# YTN1-E608_Main_V1_4.net
KiCad netlist of a schematic drawn in Altium Designer
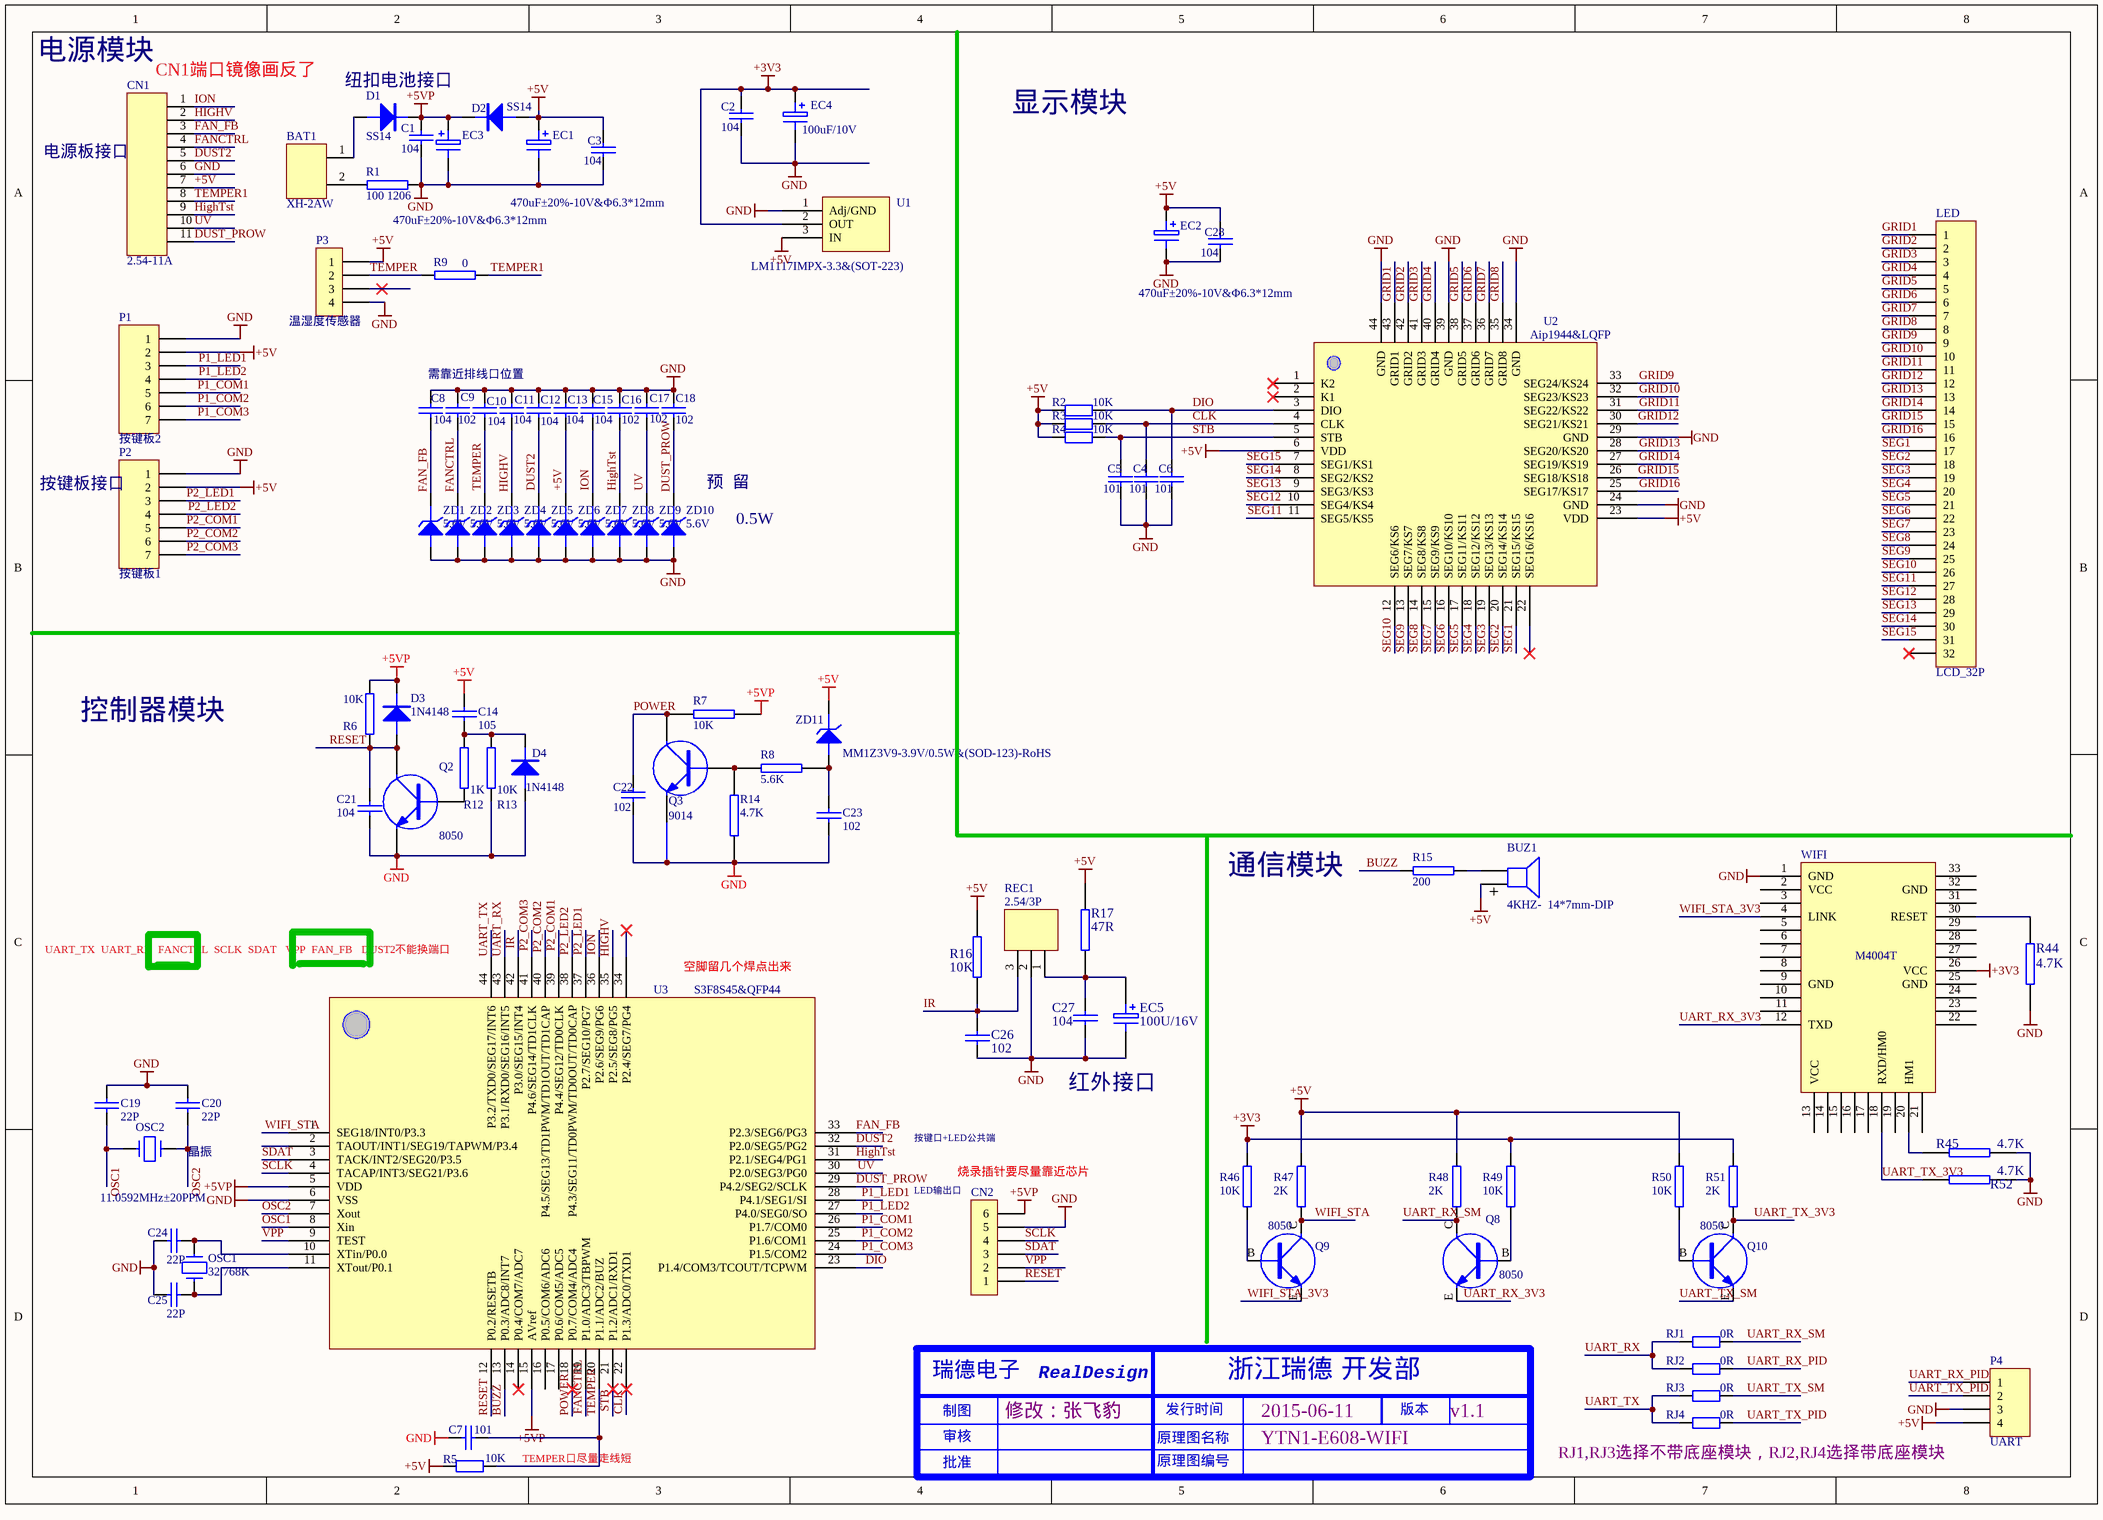
[diagram p0: YTN1-E608(Main)V1.4显示板..schdoc]

(export (version "E")
  (design (tool "Eeschema 10.0.6"))
  (components
    (comp (ref "BAT1") (value "XH-2AW") (footprint "XH-2AW-1") (libsource (lib "*") (part "250-2A")))
    (comp (ref "BUZ1")
      (value "4KHZ-  14*7mm-DIP")
      (footprint "BUZ4K-BCE")
      (libsource (lib "*") (part "SPEAKER"))
    )
    (comp (ref "C1") (value "104") (footprint "0805C") (libsource (lib "*") (part "CAP")))
    (comp (ref "C2") (value "104") (footprint "0805C") (libsource (lib "*") (part "CAP")))
    (comp (ref "C3") (value "104") (footprint "0805C") (libsource (lib "*") (part "CAP")))
    (comp (ref "C4")
      (value "101")
      (footprint "0805C")
      (description "瓷片电容、独石电容")
      (libsource (lib "*") (part "CAP"))
    )
    (comp (ref "C5")
      (value "101")
      (footprint "0805C")
      (description "瓷片电容、独石电容")
      (libsource (lib "*") (part "CAP"))
    )
    (comp (ref "C6")
      (value "101")
      (footprint "0805C")
      (description "瓷片电容、独石电容")
      (libsource (lib "*") (part "CAP"))
    )
    (comp (ref "C7")
      (value "101")
      (footprint "0805C")
      (description "瓷片电容、独石电容")
      (libsource (lib "*") (part "CAP"))
    )
    (comp (ref "C8")
      (value "104")
      (footprint "0805C")
      (description "瓷片电容、独石电容")
      (libsource (lib "*") (part "CAP"))
    )
    (comp (ref "C9")
      (value "102")
      (footprint "0805C")
      (description "瓷片电容、独石电容")
      (libsource (lib "*") (part "CAP"))
    )
    (comp (ref "C10")
      (value "104")
      (footprint "0805C")
      (description "瓷片电容、独石电容")
      (libsource (lib "*") (part "CAP"))
    )
    (comp (ref "C11")
      (value "104")
      (footprint "0805C")
      (description "瓷片电容、独石电容")
      (libsource (lib "*") (part "CAP"))
    )
    (comp (ref "C12")
      (value "104")
      (footprint "0805C")
      (description "瓷片电容、独石电容")
      (libsource (lib "*") (part "CAP"))
    )
    (comp (ref "C13")
      (value "104")
      (footprint "0805C")
      (description "瓷片电容、独石电容")
      (libsource (lib "*") (part "CAP"))
    )
    (comp (ref "C14")
      (value "105")
      (footprint "0805C")
      (description "瓷片电容、独石电容")
      (libsource (lib "*") (part "CAP"))
    )
    (comp (ref "C15")
      (value "104")
      (footprint "0805C")
      (description "瓷片电容、独石电容")
      (libsource (lib "*") (part "CAP"))
    )
    (comp (ref "C16")
      (value "102")
      (footprint "0805C")
      (description "瓷片电容、独石电容")
      (libsource (lib "*") (part "CAP"))
    )
    (comp (ref "C17")
      (value "102")
      (footprint "0805C")
      (description "瓷片电容、独石电容")
      (libsource (lib "*") (part "CAP"))
    )
    (comp (ref "C18")
      (value "102")
      (footprint "0805C")
      (description "瓷片电容、独石电容")
      (libsource (lib "*") (part "CAP"))
    )
    (comp (ref "C19")
      (value "22P")
      (footprint "0805C")
      (description "瓷片电容、独石电容")
      (libsource (lib "*") (part "CAP"))
    )
    (comp (ref "C20")
      (value "22P")
      (footprint "0805C")
      (description "瓷片电容、独石电容")
      (libsource (lib "*") (part "CAP"))
    )
    (comp (ref "C21")
      (value "104")
      (footprint "0805C")
      (description "瓷片电容、独石电容")
      (libsource (lib "*") (part "CAP"))
    )
    (comp (ref "C22")
      (value "102")
      (footprint "0805C")
      (description "瓷片电容、独石电容")
      (libsource (lib "*") (part "CAP"))
    )
    (comp (ref "C23")
      (value "102")
      (footprint "0805C")
      (description "瓷片电容、独石电容")
      (libsource (lib "*") (part "CAP"))
    )
    (comp (ref "C24") (value "22P") (footprint "0805C") (libsource (lib "*") (part "CAP")))
    (comp (ref "C25") (value "22P") (footprint "0805C") (libsource (lib "*") (part "CAP")))
    (comp (ref "C26")
      (value "102")
      (footprint "0805C")
      (description "Capacitor")
      (libsource (lib "") (part "CAP_1"))
    )
    (comp (ref "C27")
      (value "104")
      (footprint "0805C")
      (description "Capacitor")
      (libsource (lib "") (part "CAP_1"))
    )
    (comp (ref "C28") (value "104") (footprint "0805C") (libsource (lib "*") (part "CAP")))
    (comp (ref "CN1") (value "2.54-11A") (footprint "XH-11AW-1") (libsource (lib "*") (part "3.96-11A")))
    (comp (ref "CN2")
      (value "~")
      (footprint "SIP-6P")
      (description "Connector")
      (libsource (lib "*") (part "CON6"))
    )
    (comp (ref "D1")
      (value "SS14")
      (footprint "SMA")
      (description "整流二极管、开关二极管、肖特基二极管、快恢复二极管")
      (libsource (lib "*") (part "DIODE"))
    )
    (comp (ref "D2")
      (value "SS14")
      (footprint "SMA")
      (description "整流二极管、开关二极管、肖特基二极管、快恢复二极管")
      (libsource (lib "*") (part "DIODE"))
    )
    (comp (ref "D3")
      (value "1N4148")
      (footprint "SOD-123")
      (description "整流二极管、开关二极管、肖特基二极管、快恢复二极管")
      (libsource (lib "*") (part "DIODE"))
    )
    (comp (ref "D4")
      (value "1N4148")
      (footprint "SOD-123")
      (description "整流二极管、开关二极管、肖特基二极管、快恢复二极管")
      (libsource (lib "*") (part "DIODE"))
    )
    (comp (ref "EC1")
      (value "470uF±20%-10V&Φ6.3*12mm")
      (footprint "470UF10V-AI")
      (description "电解电容正极为\"1\"号脚")
      (libsource (lib "*") (part "ELECTRO"))
    )
    (comp (ref "EC2")
      (value "470uF±20%-10V&Φ6.3*12mm")
      (footprint "470UF10V-AI")
      (description "电解电容正极为\"1\"号脚")
      (libsource (lib "*") (part "ELECTRO"))
    )
    (comp (ref "EC3")
      (value "470uF±20%-10V&Φ6.3*12mm")
      (footprint "470UF10V-AI")
      (libsource (lib "") (part "ELECTRO1_1"))
    )
    (comp (ref "EC4") (value "100uF/10V") (footprint "100UF10V-AI") (libsource (lib "") (part "ELECTRO1_1")))
    (comp (ref "EC5")
      (value "100U/16V")
      (footprint "100UF16V-AI")
      (description "Electrolytic Capacitor")
      (libsource (lib "*") (part "ELECTRO1"))
    )
    (comp (ref "LED") (value "LCD_32P") (footprint "HYH") (libsource (lib "*") (part "LCD_32P")))
    (comp (ref "OSC1")
      (value "32.768K")
      (footprint "32.768J")
      (description "Crystal")
      (libsource (lib "*") (part "CRYSTAL"))
    )
    (comp (ref "OSC2")
      (value "11.0592MHz±20PPM")
      (footprint "CSA4.19MG")
      (description "Crystal")
      (libsource (lib "") (part "CRYSTAL_1"))
    )
    (comp (ref "P1")
      (value "按键板2")
      (footprint "XH-7AW-1")
      (description "Header, 7-Pin")
      (fields (field (name "PUBLISHER") "Altium Limited"))
      (libsource (lib "*") (part "Header 7"))
    )
    (comp (ref "P2")
      (value "按键板1")
      (footprint "XH-7AW-1")
      (description "Header, 7-Pin")
      (fields (field (name "PUBLISHER") "Altium Limited"))
      (libsource (lib "*") (part "Header 7"))
    )
    (comp (ref "P3")
      (value "温湿度传感器")
      (footprint "XH-4AW-1")
      (description "Connector")
      (libsource (lib "*") (part "CON4"))
    )
    (comp (ref "P4")
      (value "UART")
      (footprint "HDR1X4")
      (description "Header, 4-Pin")
      (fields (field (name "PUBLISHER") "Altium Limited"))
      (libsource (lib "Miscellaneous Connectors") (part "Header 4"))
    )
    (comp (ref "Q2")
      (value "8050")
      (footprint "SOT-23-S")
      (description "晶体管")
      (libsource (lib "") (part "NPN_1"))
    )
    (comp (ref "Q3")
      (value "9014")
      (footprint "SOT-23-S")
      (description "晶体管")
      (libsource (lib "") (part "NPN_1"))
    )
    (comp (ref "Q8")
      (value "8050")
      (footprint "SOT-23-S")
      (description "NPN Transistor")
      (libsource (lib "*") (part "NPN"))
    )
    (comp (ref "Q9")
      (value "8050")
      (footprint "SOT-23-S")
      (description "NPN Transistor")
      (libsource (lib "*") (part "NPN"))
    )
    (comp (ref "Q10")
      (value "8050")
      (footprint "SOT-23-S")
      (description "NPN Transistor")
      (libsource (lib "*") (part "NPN"))
    )
    (comp (ref "R1") (value "100 1206") (footprint "1206R") (libsource (lib "") (part "RES2_1")))
    (comp (ref "R2")
      (value "10K")
      (footprint "0805R")
      (description "Resistor")
      (fields (field (name "Comment") "Res2") (field (name "PUBLISHER") "Altium Limited"))
      (libsource (lib "*") (part "Res2"))
    )
    (comp (ref "R3")
      (value "10K")
      (footprint "0805R")
      (description "Resistor")
      (fields (field (name "Comment") "Res2") (field (name "PUBLISHER") "Altium Limited"))
      (libsource (lib "*") (part "Res2"))
    )
    (comp (ref "R4")
      (value "10K")
      (footprint "0805R")
      (description "Resistor")
      (fields (field (name "Comment") "Res2") (field (name "PUBLISHER") "Altium Limited"))
      (libsource (lib "") (part "Res2_1"))
    )
    (comp (ref "R5")
      (value "10K")
      (footprint "0805R")
      (description "Resistor")
      (fields (field (name "Comment") "Res2") (field (name "PUBLISHER") "Altium Limited"))
      (libsource (lib "*") (part "Res2"))
    )
    (comp (ref "R6") (value "10K") (footprint "0805R") (libsource (lib "") (part "RES2_1")))
    (comp (ref "R7") (value "10K") (footprint "0805R") (libsource (lib "*") (part "R")))
    (comp (ref "R8") (value "5.6K") (footprint "0805R") (libsource (lib "*") (part "R")))
    (comp (ref "R9") (value "0") (footprint "0805R") (libsource (lib "") (part "RES2_1")))
    (comp (ref "R12") (value "1K") (footprint "0805R") (libsource (lib "") (part "RES2_1")))
    (comp (ref "R13") (value "10K") (footprint "0805R") (libsource (lib "") (part "RES2_1")))
    (comp (ref "R14") (value "4.7K") (footprint "0805R") (libsource (lib "*") (part "R")))
    (comp (ref "R15") (value "200") (footprint "0805R") (libsource (lib "") (part "RES2_1")))
    (comp (ref "R16") (value "10K") (footprint "0805R") (libsource (lib "*") (part "RES2")))
    (comp (ref "R17") (value "47R") (footprint "0805-1") (libsource (lib "*") (part "RES2")))
    (comp (ref "R44") (value "4.7K") (footprint "0805R") (libsource (lib "*") (part "RES2")))
    (comp (ref "R45") (value "4.7K") (footprint "0805R") (libsource (lib "*") (part "RES2")))
    (comp (ref "R46") (value "10K") (footprint "0805R") (libsource (lib "") (part "RES2_1")))
    (comp (ref "R47") (value "2K") (footprint "0805R") (libsource (lib "") (part "RES2_1")))
    (comp (ref "R48") (value "2K") (footprint "0805R") (libsource (lib "") (part "RES2_1")))
    (comp (ref "R49") (value "10K") (footprint "0805R") (libsource (lib "") (part "RES2_1")))
    (comp (ref "R50") (value "10K") (footprint "0805R") (libsource (lib "") (part "RES2_1")))
    (comp (ref "R51") (value "2K") (footprint "0805R") (libsource (lib "") (part "RES2_1")))
    (comp (ref "R52") (value "4.7K") (footprint "0805R") (libsource (lib "*") (part "RES2")))
    (comp (ref "REC1") (value "2.54/3P") (footprint "XH-3AW-1") (libsource (lib "*") (part "3.96-3A")))
    (comp (ref "RJ1")
      (value "0R")
      (footprint "AXIAL-0.4")
      (description "Resistor")
      (fields (field (name "PUBLISHER") "Altium Limited"))
      (libsource (lib "Miscellaneous Devices") (part "Res2"))
    )
    (comp (ref "RJ2")
      (value "0R")
      (footprint "AXIAL-0.4")
      (description "Resistor")
      (fields (field (name "PUBLISHER") "Altium Limited"))
      (libsource (lib "Miscellaneous Devices") (part "Res2"))
    )
    (comp (ref "RJ3")
      (value "0R")
      (footprint "AXIAL-0.4")
      (description "Resistor")
      (fields (field (name "PUBLISHER") "Altium Limited"))
      (libsource (lib "Miscellaneous Devices") (part "Res2"))
    )
    (comp (ref "RJ4")
      (value "0R")
      (footprint "AXIAL-0.4")
      (description "Resistor")
      (fields (field (name "PUBLISHER") "Altium Limited"))
      (libsource (lib "Miscellaneous Devices") (part "Res2"))
    )
    (comp (ref "U1") (value "LM1117IMPX-3.3&(SOT-223)") (libsource (lib "*") (part "LM1117-3.3V")))
    (comp (ref "U2") (value "Aip1944&LQFP") (footprint "QFP44") (libsource (lib "*") (part "Aip1944&LQFP")))
    (comp (ref "U3") (value "S3F8S45&QFP44") (footprint "QFP44") (libsource (lib "*") (part "S3F8S45&QFP44")))
    (comp (ref "WIFI") (value "M4004T") (footprint "WIFI") (libsource (lib "*") (part "WIFI")))
    (comp (ref "ZD1") (value "5.6V") (footprint "SOD-123") (libsource (lib "*") (part "ZD")))
    (comp (ref "ZD2") (value "5.6V") (footprint "SOD-123") (libsource (lib "*") (part "ZD")))
    (comp (ref "ZD3") (value "5.6V") (footprint "SOD-123") (libsource (lib "*") (part "ZD")))
    (comp (ref "ZD4") (value "5.6V") (footprint "SOD-123") (libsource (lib "*") (part "ZD")))
    (comp (ref "ZD5") (value "5.6V") (footprint "SOD-123") (libsource (lib "*") (part "ZD")))
    (comp (ref "ZD6") (value "5.6V") (footprint "SOD-123") (libsource (lib "*") (part "ZD")))
    (comp (ref "ZD7") (value "5.6V") (footprint "SOD-123") (libsource (lib "*") (part "ZD")))
    (comp (ref "ZD8") (value "5.6V") (footprint "SOD-123") (libsource (lib "*") (part "ZD")))
    (comp (ref "ZD9") (value "5.6V") (footprint "SOD-123") (libsource (lib "*") (part "ZD")))
    (comp (ref "ZD10") (value "5.6V") (footprint "SOD-123") (libsource (lib "*") (part "ZD")))
    (comp (ref "ZD11")
      (value "MM1Z3V9-3.9V/0.5W&(SOD-123)-RoHS")
      (footprint "SOD-123")
      (libsource (lib "*") (part "ZD"))
    )
  )
  (nets
    (net (code "1") (name "+3V3") (class "Default")
      (node (ref "C2") (pin "1") (pintype "passive"))
      (node (ref "EC4") (pin "1") (pintype "passive"))
      (node (ref "R46") (pin "1") (pintype "passive"))
      (node (ref "R49") (pin "1") (pintype "passive"))
      (node (ref "R51") (pin "1") (pintype "passive"))
      (node (ref "U1") (pin "2") (pinfunction "OUT_2") (pintype "passive"))
      (node (ref "WIFI") (pin "26") (pinfunction "VCC_26") (pintype "passive"))
    )
    (net (code "2") (name "+5V") (class "Default")
      (node (ref "BUZ1") (pin "1") (pinfunction "1_1") (pintype "passive"))
      (node (ref "C13") (pin "2") (pintype "passive"))
      (node (ref "C14") (pin "1") (pintype "passive"))
      (node (ref "C28") (pin "1") (pintype "passive"))
      (node (ref "C3") (pin "1") (pintype "passive"))
      (node (ref "CN1") (pin "7") (pinfunction "7_7") (pintype "passive"))
      (node (ref "D2") (pin "A") (pintype "passive"))
      (node (ref "EC1") (pin "1") (pintype "passive"))
      (node (ref "EC2") (pin "1") (pintype "passive"))
      (node (ref "P1") (pin "2") (pinfunction "2_2") (pintype "passive"))
      (node (ref "P2") (pin "2") (pinfunction "2_2") (pintype "passive"))
      (node (ref "P3") (pin "1") (pinfunction "1_1") (pintype "passive"))
      (node (ref "P4") (pin "4") (pinfunction "4_4") (pintype "passive"))
      (node (ref "R16") (pin "2") (pinfunction "2_2") (pintype "passive"))
      (node (ref "R17") (pin "2") (pinfunction "2_2") (pintype "passive"))
      (node (ref "R2") (pin "2") (pinfunction "2_2") (pintype "passive"))
      (node (ref "R3") (pin "2") (pinfunction "2_2") (pintype "passive"))
      (node (ref "R4") (pin "1") (pinfunction "1_1") (pintype "passive"))
      (node (ref "R47") (pin "1") (pintype "passive"))
      (node (ref "R48") (pin "1") (pintype "passive"))
      (node (ref "R5") (pin "2") (pinfunction "2_2") (pintype "passive"))
      (node (ref "R50") (pin "1") (pintype "passive"))
      (node (ref "U1") (pin "3") (pinfunction "IN_3") (pintype "passive"))
      (node (ref "U2") (pin "23") (pinfunction "VDD_23") (pintype "passive"))
      (node (ref "U2") (pin "6") (pinfunction "VDD_6") (pintype "passive"))
      (node (ref "ZD11") (pin "K") (pintype "passive"))
      (node (ref "ZD6") (pin "K") (pintype "passive"))
    )
    (net (code "3") (name "+5VP") (class "Default")
      (node (ref "C1") (pin "1") (pintype "passive"))
      (node (ref "CN2") (pin "6") (pinfunction "6_6") (pintype "passive"))
      (node (ref "D1") (pin "K") (pintype "passive"))
      (node (ref "D2") (pin "K") (pintype "passive"))
      (node (ref "D3") (pin "K") (pintype "passive"))
      (node (ref "EC3") (pin "1") (pintype "passive"))
      (node (ref "R6") (pin "2") (pintype "passive"))
      (node (ref "R7") (pin "1") (pinfunction "1_1") (pintype "passive"))
      (node (ref "U3") (pin "15") (pinfunction "AVref_15") (pintype "passive"))
      (node (ref "U3") (pin "5") (pinfunction "VDD_5") (pintype "passive"))
    )
    (net (code "4") (name "/BUZZ") (class "Default")
      (node (ref "R15") (pin "1") (pintype "passive"))
      (node (ref "U3") (pin "13") (pinfunction "P0.3/ADC8/INT7_13") (pintype "passive"))
    )
    (net (code "5") (name "/CLK") (class "Default")
      (node (ref "C4") (pin "1") (pintype "passive"))
      (node (ref "R3") (pin "1") (pinfunction "1_1") (pintype "passive"))
      (node (ref "U2") (pin "4") (pinfunction "CLK_4") (pintype "passive"))
      (node (ref "U3") (pin "22") (pinfunction "P1.3/ADC0/TXD1_22") (pintype "passive"))
    )
    (net (code "6") (name "/DIO") (class "Default")
      (node (ref "C6") (pin "1") (pintype "passive"))
      (node (ref "R2") (pin "1") (pinfunction "1_1") (pintype "passive"))
      (node (ref "U2") (pin "3") (pinfunction "DIO_3") (pintype "passive"))
      (node (ref "U3") (pin "23") (pinfunction "P1.4/COM3/TCOUT/TCPWM_23") (pintype "passive"))
    )
    (net (code "7") (name "/DUST2") (class "Default")
      (node (ref "C12") (pin "2") (pintype "passive"))
      (node (ref "CN1") (pin "5") (pinfunction "5_5") (pintype "passive"))
      (node (ref "U3") (pin "32") (pinfunction "P2.0/SEG5/PG2_32") (pintype "passive"))
      (node (ref "ZD5") (pin "K") (pintype "passive"))
    )
    (net (code "8") (name "/DUST_PROW") (class "Default")
      (node (ref "C18") (pin "2") (pintype "passive"))
      (node (ref "CN1") (pin "11") (pinfunction "11_11") (pintype "passive"))
      (node (ref "U3") (pin "29") (pinfunction "P4.2/SEG2/SCLK_29") (pintype "passive"))
      (node (ref "ZD10") (pin "K") (pintype "passive"))
    )
    (net (code "9") (name "/FANCTRL") (class "Default")
      (node (ref "C9") (pin "2") (pintype "passive"))
      (node (ref "CN1") (pin "4") (pinfunction "4_4") (pintype "passive"))
      (node (ref "U3") (pin "19") (pinfunction "P1.0/ADC3/TBPWM_19") (pintype "passive"))
      (node (ref "ZD2") (pin "K") (pintype "passive"))
    )
    (net (code "10") (name "/FAN_FB") (class "Default")
      (node (ref "C8") (pin "2") (pintype "passive"))
      (node (ref "CN1") (pin "3") (pinfunction "3_3") (pintype "passive"))
      (node (ref "U3") (pin "33") (pinfunction "P2.3/SEG6/PG3_33") (pintype "passive"))
      (node (ref "ZD1") (pin "K") (pintype "passive"))
    )
    (net (code "11") (name "/GRID1") (class "Default")
      (node (ref "LED") (pin "1") (pinfunction "1_1") (pintype "passive"))
      (node (ref "U2") (pin "43") (pinfunction "GRID1_43") (pintype "passive"))
    )
    (net (code "12") (name "/GRID2") (class "Default")
      (node (ref "LED") (pin "2") (pinfunction "2_2") (pintype "passive"))
      (node (ref "U2") (pin "42") (pinfunction "GRID2_42") (pintype "passive"))
    )
    (net (code "13") (name "/GRID3") (class "Default")
      (node (ref "LED") (pin "3") (pinfunction "3_3") (pintype "passive"))
      (node (ref "U2") (pin "41") (pinfunction "GRID3_41") (pintype "passive"))
    )
    (net (code "14") (name "/GRID4") (class "Default")
      (node (ref "LED") (pin "4") (pinfunction "4_4") (pintype "passive"))
      (node (ref "U2") (pin "40") (pinfunction "GRID4_40") (pintype "passive"))
    )
    (net (code "15") (name "/GRID5") (class "Default")
      (node (ref "LED") (pin "5") (pinfunction "5_5") (pintype "passive"))
      (node (ref "U2") (pin "38") (pinfunction "GRID5_38") (pintype "passive"))
    )
    (net (code "16") (name "/GRID6") (class "Default")
      (node (ref "LED") (pin "6") (pinfunction "6_6") (pintype "passive"))
      (node (ref "U2") (pin "37") (pinfunction "GRID6_37") (pintype "passive"))
    )
    (net (code "17") (name "/GRID7") (class "Default")
      (node (ref "LED") (pin "7") (pinfunction "7_7") (pintype "passive"))
      (node (ref "U2") (pin "36") (pinfunction "GRID7_36") (pintype "passive"))
    )
    (net (code "18") (name "/GRID8") (class "Default")
      (node (ref "LED") (pin "8") (pinfunction "8_8") (pintype "passive"))
      (node (ref "U2") (pin "35") (pinfunction "GRID8_35") (pintype "passive"))
    )
    (net (code "19") (name "/GRID9") (class "Default")
      (node (ref "LED") (pin "9") (pinfunction "9_9") (pintype "passive"))
      (node (ref "U2") (pin "33") (pinfunction "SEG24/KS24_33") (pintype "passive"))
    )
    (net (code "20") (name "/GRID10") (class "Default")
      (node (ref "LED") (pin "10") (pinfunction "10_10") (pintype "passive"))
      (node (ref "U2") (pin "32") (pinfunction "SEG23/KS23_32") (pintype "passive"))
    )
    (net (code "21") (name "/GRID11") (class "Default")
      (node (ref "LED") (pin "11") (pinfunction "11_11") (pintype "passive"))
      (node (ref "U2") (pin "31") (pinfunction "SEG22/KS22_31") (pintype "passive"))
    )
    (net (code "22") (name "/GRID12") (class "Default")
      (node (ref "LED") (pin "12") (pinfunction "12_12") (pintype "passive"))
      (node (ref "U2") (pin "30") (pinfunction "SEG21/KS21_30") (pintype "passive"))
    )
    (net (code "23") (name "/GRID13") (class "Default")
      (node (ref "LED") (pin "13") (pinfunction "13_13") (pintype "passive"))
      (node (ref "U2") (pin "28") (pinfunction "SEG20/KS20_28") (pintype "passive"))
    )
    (net (code "24") (name "/GRID14") (class "Default")
      (node (ref "LED") (pin "14") (pinfunction "14_14") (pintype "passive"))
      (node (ref "U2") (pin "27") (pinfunction "SEG19/KS19_27") (pintype "passive"))
    )
    (net (code "25") (name "/GRID15") (class "Default")
      (node (ref "LED") (pin "15") (pinfunction "15_15") (pintype "passive"))
      (node (ref "U2") (pin "26") (pinfunction "SEG18/KS18_26") (pintype "passive"))
    )
    (net (code "26") (name "/GRID16") (class "Default")
      (node (ref "LED") (pin "16") (pinfunction "16_16") (pintype "passive"))
      (node (ref "U2") (pin "25") (pinfunction "SEG17/KS17_25") (pintype "passive"))
    )
    (net (code "27") (name "/HIGHV") (class "Default")
      (node (ref "C11") (pin "2") (pintype "passive"))
      (node (ref "CN1") (pin "2") (pinfunction "2_2") (pintype "passive"))
      (node (ref "U3") (pin "35") (pinfunction "P2.5/SEG8/PG5_35") (pintype "passive"))
      (node (ref "ZD4") (pin "K") (pintype "passive"))
    )
    (net (code "28") (name "/HighTst") (class "Default")
      (node (ref "C16") (pin "2") (pintype "passive"))
      (node (ref "CN1") (pin "9") (pinfunction "9_9") (pintype "passive"))
      (node (ref "U3") (pin "31") (pinfunction "P2.1/SEG4/PG1_31") (pintype "passive"))
      (node (ref "ZD8") (pin "K") (pintype "passive"))
    )
    (net (code "29") (name "/ION") (class "Default")
      (node (ref "C15") (pin "2") (pintype "passive"))
      (node (ref "CN1") (pin "1") (pinfunction "1_1") (pintype "passive"))
      (node (ref "U3") (pin "36") (pinfunction "P2.6/SEG9/PG6_36") (pintype "passive"))
      (node (ref "ZD7") (pin "K") (pintype "passive"))
    )
    (net (code "30") (name "/IR") (class "Default")
      (node (ref "C26") (pin "1") (pinfunction "1_1") (pintype "passive"))
      (node (ref "R16") (pin "1") (pinfunction "1_1") (pintype "passive"))
      (node (ref "REC1") (pin "3") (pinfunction "20_3") (pintype "passive"))
      (node (ref "U3") (pin "42") (pinfunction "P3.0/SEG15/INT4_42") (pintype "passive"))
    )
    (net (code "31") (name "/OSC1") (class "Default")
      (node (ref "C19") (pin "1") (pintype "passive"))
      (node (ref "OSC2") (pin "1") (pinfunction "1_1") (pintype "passive"))
      (node (ref "U3") (pin "8") (pinfunction "Xin_8") (pintype "passive"))
    )
    (net (code "32") (name "/OSC2") (class "Default")
      (node (ref "C20") (pin "1") (pintype "passive"))
      (node (ref "OSC2") (pin "3") (pinfunction "3_3") (pintype "passive"))
      (node (ref "U3") (pin "7") (pinfunction "Xout_7") (pintype "passive"))
    )
    (net (code "33") (name "/P1_COM1") (class "Default")
      (node (ref "P1") (pin "5") (pinfunction "5_5") (pintype "passive"))
      (node (ref "U3") (pin "26") (pinfunction "P1.7/COM0_26") (pintype "passive"))
    )
    (net (code "34") (name "/P1_COM2") (class "Default")
      (node (ref "P1") (pin "6") (pinfunction "6_6") (pintype "passive"))
      (node (ref "U3") (pin "25") (pinfunction "P1.6/COM1_25") (pintype "passive"))
    )
    (net (code "35") (name "/P1_COM3") (class "Default")
      (node (ref "P1") (pin "7") (pinfunction "7_7") (pintype "passive"))
      (node (ref "U3") (pin "24") (pinfunction "P1.5/COM2_24") (pintype "passive"))
    )
    (net (code "36") (name "/P1_LED1") (class "Default")
      (node (ref "P1") (pin "3") (pinfunction "3_3") (pintype "passive"))
      (node (ref "U3") (pin "28") (pinfunction "P4.1/SEG1/SI_28") (pintype "passive"))
    )
    (net (code "37") (name "/P1_LED2") (class "Default")
      (node (ref "P1") (pin "4") (pinfunction "4_4") (pintype "passive"))
      (node (ref "U3") (pin "27") (pinfunction "P4.0/SEG0/SO_27") (pintype "passive"))
    )
    (net (code "38") (name "/P2_COM1") (class "Default")
      (node (ref "P2") (pin "5") (pinfunction "5_5") (pintype "passive"))
      (node (ref "U3") (pin "39") (pinfunction "P4.4/SEG12/TD0CLK_39") (pintype "passive"))
    )
    (net (code "39") (name "/P2_COM2") (class "Default")
      (node (ref "P2") (pin "6") (pinfunction "6_6") (pintype "passive"))
      (node (ref "U3") (pin "40") (pinfunction "P4.5/SEG13/TD1PWM/TD1OUT/TD1CAP_40") (pintype "passive"))
    )
    (net (code "40") (name "/P2_COM3") (class "Default")
      (node (ref "P2") (pin "7") (pinfunction "7_7") (pintype "passive"))
      (node (ref "U3") (pin "41") (pinfunction "P4.6/SEG14/TD1CLK_41") (pintype "passive"))
    )
    (net (code "41") (name "/P2_LED1") (class "Default")
      (node (ref "P2") (pin "3") (pinfunction "3_3") (pintype "passive"))
      (node (ref "U3") (pin "37") (pinfunction "P2.7/SEG10/PG7_37") (pintype "passive"))
    )
    (net (code "42") (name "/P2_LED2") (class "Default")
      (node (ref "P2") (pin "4") (pinfunction "4_4") (pintype "passive"))
      (node (ref "U3") (pin "38") (pinfunction "P4.3/SEG11/TD0PWM/TD0OUT/TD0CAP_38") (pintype "passive"))
    )
    (net (code "43") (name "/POWER") (class "Default")
      (node (ref "C22") (pin "1") (pintype "passive"))
      (node (ref "Q3") (pin "C") (pintype "passive"))
      (node (ref "R7") (pin "2") (pinfunction "2_2") (pintype "passive"))
      (node (ref "U3") (pin "18") (pinfunction "P0.7/COM4/ADC4_18") (pintype "passive"))
    )
    (net (code "44") (name "/RESET") (class "Default")
      (node (ref "C21") (pin "1") (pintype "passive"))
      (node (ref "CN2") (pin "1") (pinfunction "1_1") (pintype "passive"))
      (node (ref "D3") (pin "A") (pintype "passive"))
      (node (ref "Q2") (pin "C") (pintype "passive"))
      (node (ref "R6") (pin "1") (pintype "passive"))
      (node (ref "U3") (pin "12") (pinfunction "P0.2/RESETB_12") (pintype "passive"))
    )
    (net (code "45") (name "/SCLK") (class "Default")
      (node (ref "CN2") (pin "4") (pinfunction "4_4") (pintype "passive"))
      (node (ref "U3") (pin "4") (pinfunction "TACAP/INT3/SEG21/P3.6_4") (pintype "passive"))
    )
    (net (code "46") (name "/SDAT") (class "Default")
      (node (ref "CN2") (pin "3") (pinfunction "3_3") (pintype "passive"))
      (node (ref "U3") (pin "3") (pinfunction "TACK/INT2/SEG20/P3.5_3") (pintype "passive"))
    )
    (net (code "47") (name "/SEG1") (class "Default")
      (node (ref "LED") (pin "17") (pinfunction "17_17") (pintype "passive"))
      (node (ref "U2") (pin "21") (pinfunction "SEG15/KS15_21") (pintype "passive"))
    )
    (net (code "48") (name "/SEG2") (class "Default")
      (node (ref "LED") (pin "18") (pinfunction "18_18") (pintype "passive"))
      (node (ref "U2") (pin "20") (pinfunction "SEG14/KS14_20") (pintype "passive"))
    )
    (net (code "49") (name "/SEG3") (class "Default")
      (node (ref "LED") (pin "19") (pinfunction "19_19") (pintype "passive"))
      (node (ref "U2") (pin "19") (pinfunction "SEG13/KS13_19") (pintype "passive"))
    )
    (net (code "50") (name "/SEG4") (class "Default")
      (node (ref "LED") (pin "20") (pinfunction "20_20") (pintype "passive"))
      (node (ref "U2") (pin "18") (pinfunction "SEG12/KS12_18") (pintype "passive"))
    )
    (net (code "51") (name "/SEG5") (class "Default")
      (node (ref "LED") (pin "21") (pinfunction "21_21") (pintype "passive"))
      (node (ref "U2") (pin "17") (pinfunction "SEG11/KS11_17") (pintype "passive"))
    )
    (net (code "52") (name "/SEG6") (class "Default")
      (node (ref "LED") (pin "22") (pinfunction "22_22") (pintype "passive"))
      (node (ref "U2") (pin "16") (pinfunction "SEG10/KS10_16") (pintype "passive"))
    )
    (net (code "53") (name "/SEG7") (class "Default")
      (node (ref "LED") (pin "23") (pinfunction "23_23") (pintype "passive"))
      (node (ref "U2") (pin "15") (pinfunction "SEG9/KS9_15") (pintype "passive"))
    )
    (net (code "54") (name "/SEG8") (class "Default")
      (node (ref "LED") (pin "24") (pinfunction "24_24") (pintype "passive"))
      (node (ref "U2") (pin "14") (pinfunction "SEG8/KS8_14") (pintype "passive"))
    )
    (net (code "55") (name "/SEG9") (class "Default")
      (node (ref "LED") (pin "25") (pinfunction "25_25") (pintype "passive"))
      (node (ref "U2") (pin "13") (pinfunction "SEG7/KS7_13") (pintype "passive"))
    )
    (net (code "56") (name "/SEG10") (class "Default")
      (node (ref "LED") (pin "26") (pinfunction "26_26") (pintype "passive"))
      (node (ref "U2") (pin "12") (pinfunction "SEG6/KS6_12") (pintype "passive"))
    )
    (net (code "57") (name "/SEG11") (class "Default")
      (node (ref "LED") (pin "27") (pinfunction "27_27") (pintype "passive"))
      (node (ref "U2") (pin "11") (pinfunction "SEG5/KS5_11") (pintype "passive"))
    )
    (net (code "58") (name "/SEG12") (class "Default")
      (node (ref "LED") (pin "28") (pinfunction "28_28") (pintype "passive"))
      (node (ref "U2") (pin "10") (pinfunction "SEG4/KS4_10") (pintype "passive"))
    )
    (net (code "59") (name "/SEG13") (class "Default")
      (node (ref "LED") (pin "29") (pinfunction "29_29") (pintype "passive"))
      (node (ref "U2") (pin "9") (pinfunction "SEG3/KS3_9") (pintype "passive"))
    )
    (net (code "60") (name "/SEG14") (class "Default")
      (node (ref "LED") (pin "30") (pinfunction "30_30") (pintype "passive"))
      (node (ref "U2") (pin "8") (pinfunction "SEG2/KS2_8") (pintype "passive"))
    )
    (net (code "61") (name "/SEG15") (class "Default")
      (node (ref "LED") (pin "31") (pinfunction "31_31") (pintype "passive"))
      (node (ref "U2") (pin "7") (pinfunction "SEG1/KS1_7") (pintype "passive"))
    )
    (net (code "62") (name "/STB") (class "Default")
      (node (ref "C5") (pin "1") (pintype "passive"))
      (node (ref "R4") (pin "2") (pinfunction "2_2") (pintype "passive"))
      (node (ref "U2") (pin "5") (pinfunction "STB_5") (pintype "passive"))
      (node (ref "U3") (pin "21") (pinfunction "P1.2/ADC1/RXD1_21") (pintype "passive"))
    )
    (net (code "63") (name "/TEMPER") (class "Default")
      (node (ref "C10") (pin "2") (pintype "passive"))
      (node (ref "C7") (pin "1") (pintype "passive"))
      (node (ref "P3") (pin "2") (pinfunction "2_2") (pintype "passive"))
      (node (ref "R5") (pin "1") (pinfunction "1_1") (pintype "passive"))
      (node (ref "R9") (pin "1") (pintype "passive"))
      (node (ref "U3") (pin "20") (pinfunction "P1.1/ADC2/BUZ_20") (pintype "passive"))
      (node (ref "ZD3") (pin "K") (pintype "passive"))
    )
    (net (code "64") (name "/TEMPER1") (class "Default")
      (node (ref "CN1") (pin "8") (pinfunction "8_8") (pintype "passive"))
      (node (ref "R9") (pin "2") (pintype "passive"))
    )
    (net (code "65") (name "/UART_RX") (class "Default")
      (node (ref "RJ1") (pin "1") (pinfunction "1_1") (pintype "passive"))
      (node (ref "RJ2") (pin "1") (pinfunction "1_1") (pintype "passive"))
      (node (ref "U3") (pin "43") (pinfunction "P3.1/RXD0/SEG16/INT5_43") (pintype "passive"))
    )
    (net (code "66") (name "/UART_RX_3V3") (class "Default")
      (node (ref "Q8") (pin "E") (pintype "passive"))
      (node (ref "WIFI") (pin "12") (pinfunction "TXD_12") (pintype "passive"))
    )
    (net (code "67") (name "/UART_RX_PID") (class "Default")
      (node (ref "P4") (pin "1") (pinfunction "1_1") (pintype "passive"))
      (node (ref "RJ2") (pin "2") (pinfunction "2_2") (pintype "passive"))
    )
    (net (code "68") (name "/UART_RX_SM") (class "Default")
      (node (ref "Q8") (pin "C") (pintype "passive"))
      (node (ref "R48") (pin "2") (pintype "passive"))
      (node (ref "RJ1") (pin "2") (pinfunction "2_2") (pintype "passive"))
    )
    (net (code "69") (name "/UART_TX") (class "Default")
      (node (ref "RJ3") (pin "1") (pinfunction "1_1") (pintype "passive"))
      (node (ref "RJ4") (pin "1") (pinfunction "1_1") (pintype "passive"))
      (node (ref "U3") (pin "44") (pinfunction "P3.2/TXD0/SEG17/INT6_44") (pintype "passive"))
    )
    (net (code "70") (name "/UART_TX_3V3") (class "Default")
      (node (ref "Q10") (pin "C") (pintype "passive"))
      (node (ref "R51") (pin "2") (pintype "passive"))
      (node (ref "R52") (pin "2") (pinfunction "2_2") (pintype "passive"))
      (node (ref "WIFI") (pin "18") (pinfunction "RXD/HM0_18") (pintype "passive"))
    )
    (net (code "71") (name "/UART_TX_PID") (class "Default")
      (node (ref "P4") (pin "2") (pinfunction "2_2") (pintype "passive"))
      (node (ref "RJ4") (pin "2") (pinfunction "2_2") (pintype "passive"))
    )
    (net (code "72") (name "/UART_TX_SM") (class "Default")
      (node (ref "Q10") (pin "E") (pintype "passive"))
      (node (ref "RJ3") (pin "2") (pinfunction "2_2") (pintype "passive"))
    )
    (net (code "73") (name "/UV") (class "Default")
      (node (ref "C17") (pin "2") (pintype "passive"))
      (node (ref "CN1") (pin "10") (pinfunction "10_10") (pintype "passive"))
      (node (ref "U3") (pin "30") (pinfunction "P2.0/SEG3/PG0_30") (pintype "passive"))
      (node (ref "ZD9") (pin "K") (pintype "passive"))
    )
    (net (code "74") (name "/VPP") (class "Default")
      (node (ref "CN2") (pin "2") (pinfunction "2_2") (pintype "passive"))
      (node (ref "U3") (pin "9") (pinfunction "TEST_9") (pintype "passive"))
    )
    (net (code "75") (name "/WIFI_STA") (class "Default")
      (node (ref "Q9") (pin "C") (pintype "passive"))
      (node (ref "R47") (pin "2") (pintype "passive"))
      (node (ref "U3") (pin "1") (pinfunction "SEG18/INT0/P3.3_1") (pintype "passive"))
    )
    (net (code "76") (name "/WIFI_STA_3V3") (class "Default")
      (node (ref "Q9") (pin "E") (pintype "passive"))
      (node (ref "WIFI") (pin "4") (pinfunction "LINK_4") (pintype "passive"))
    )
    (net (code "77") (name "GND") (class "Default")
      (node (ref "C1") (pin "2") (pintype "passive"))
      (node (ref "C10") (pin "1") (pintype "passive"))
      (node (ref "C11") (pin "1") (pintype "passive"))
      (node (ref "C12") (pin "1") (pintype "passive"))
      (node (ref "C13") (pin "1") (pintype "passive"))
      (node (ref "C15") (pin "1") (pintype "passive"))
      (node (ref "C16") (pin "1") (pintype "passive"))
      (node (ref "C17") (pin "1") (pintype "passive"))
      (node (ref "C18") (pin "1") (pintype "passive"))
      (node (ref "C19") (pin "2") (pintype "passive"))
      (node (ref "C2") (pin "2") (pintype "passive"))
      (node (ref "C20") (pin "2") (pintype "passive"))
      (node (ref "C21") (pin "2") (pintype "passive"))
      (node (ref "C22") (pin "2") (pintype "passive"))
      (node (ref "C23") (pin "2") (pintype "passive"))
      (node (ref "C24") (pin "1") (pintype "passive"))
      (node (ref "C25") (pin "1") (pintype "passive"))
      (node (ref "C26") (pin "2") (pinfunction "2_2") (pintype "passive"))
      (node (ref "C27") (pin "2") (pinfunction "2_2") (pintype "passive"))
      (node (ref "C28") (pin "2") (pintype "passive"))
      (node (ref "C3") (pin "2") (pintype "passive"))
      (node (ref "C4") (pin "2") (pintype "passive"))
      (node (ref "C5") (pin "2") (pintype "passive"))
      (node (ref "C6") (pin "2") (pintype "passive"))
      (node (ref "C7") (pin "2") (pintype "passive"))
      (node (ref "C8") (pin "1") (pintype "passive"))
      (node (ref "C9") (pin "1") (pintype "passive"))
      (node (ref "CN1") (pin "6") (pinfunction "6_6") (pintype "passive"))
      (node (ref "CN2") (pin "5") (pinfunction "5_5") (pintype "passive"))
      (node (ref "D4") (pin "A") (pintype "passive"))
      (node (ref "EC1") (pin "2") (pintype "passive"))
      (node (ref "EC2") (pin "2") (pintype "passive"))
      (node (ref "EC3") (pin "2") (pintype "passive"))
      (node (ref "EC4") (pin "2") (pintype "passive"))
      (node (ref "EC5") (pin "2") (pinfunction "2_2") (pintype "passive"))
      (node (ref "P1") (pin "1") (pinfunction "1_1") (pintype "passive"))
      (node (ref "P2") (pin "1") (pinfunction "1_1") (pintype "passive"))
      (node (ref "P3") (pin "4") (pinfunction "4_4") (pintype "passive"))
      (node (ref "P4") (pin "3") (pinfunction "3_3") (pintype "passive"))
      (node (ref "Q2") (pin "E") (pintype "passive"))
      (node (ref "Q3") (pin "E") (pintype "passive"))
      (node (ref "R1") (pin "2") (pintype "passive"))
      (node (ref "R13") (pin "1") (pintype "passive"))
      (node (ref "R14") (pin "1") (pinfunction "1_1") (pintype "passive"))
      (node (ref "R44") (pin "2") (pinfunction "2_2") (pintype "passive"))
      (node (ref "R45") (pin "1") (pinfunction "1_1") (pintype "passive"))
      (node (ref "R52") (pin "1") (pinfunction "1_1") (pintype "passive"))
      (node (ref "REC1") (pin "2") (pinfunction "2_2") (pintype "passive"))
      (node (ref "U1") (pin "1") (pinfunction "Adj/GND_1") (pintype "passive"))
      (node (ref "U2") (pin "24") (pinfunction "GND_24") (pintype "passive"))
      (node (ref "U2") (pin "29") (pinfunction "GND_29") (pintype "passive"))
      (node (ref "U2") (pin "34") (pinfunction "GND_34") (pintype "passive"))
      (node (ref "U2") (pin "39") (pinfunction "GND_39") (pintype "passive"))
      (node (ref "U2") (pin "44") (pinfunction "GND_44") (pintype "passive"))
      (node (ref "U3") (pin "6") (pinfunction "VSS_6") (pintype "passive"))
      (node (ref "WIFI") (pin "1") (pinfunction "GND_1") (pintype "passive"))
      (node (ref "ZD1") (pin "A") (pintype "passive"))
      (node (ref "ZD10") (pin "A") (pintype "passive"))
      (node (ref "ZD2") (pin "A") (pintype "passive"))
      (node (ref "ZD3") (pin "A") (pintype "passive"))
      (node (ref "ZD4") (pin "A") (pintype "passive"))
      (node (ref "ZD5") (pin "A") (pintype "passive"))
      (node (ref "ZD6") (pin "A") (pintype "passive"))
      (node (ref "ZD7") (pin "A") (pintype "passive"))
      (node (ref "ZD8") (pin "A") (pintype "passive"))
      (node (ref "ZD9") (pin "A") (pintype "passive"))
    )
    (net (code "78") (name "Net-(BAT1-Pad1)") (class "Default")
      (node (ref "BAT1") (pin "1") (pinfunction "1_1") (pintype "passive"))
      (node (ref "D1") (pin "A") (pintype "passive"))
    )
    (net (code "79") (name "Net-(BAT1-Pad2)") (class "Default")
      (node (ref "BAT1") (pin "2") (pinfunction "2_2") (pintype "passive"))
      (node (ref "R1") (pin "1") (pintype "passive"))
    )
    (net (code "80") (name "Net-(BUZ1-Pad2)") (class "Default")
      (node (ref "BUZ1") (pin "2") (pinfunction "2_2") (pintype "passive"))
      (node (ref "R15") (pin "2") (pintype "passive"))
    )
    (net (code "81") (name "Net-(C14-Pad2)") (class "Default")
      (node (ref "C14") (pin "2") (pintype "passive"))
      (node (ref "D4") (pin "K") (pintype "passive"))
      (node (ref "R12") (pin "2") (pintype "passive"))
      (node (ref "R13") (pin "2") (pintype "passive"))
    )
    (net (code "82") (name "Net-(C23-Pad1)") (class "Default")
      (node (ref "C23") (pin "1") (pintype "passive"))
      (node (ref "R8") (pin "1") (pinfunction "1_1") (pintype "passive"))
      (node (ref "ZD11") (pin "A") (pintype "passive"))
    )
    (net (code "83") (name "Net-(C27-Pad1)") (class "Default")
      (node (ref "C27") (pin "1") (pinfunction "1_1") (pintype "passive"))
      (node (ref "EC5") (pin "1") (pinfunction "1_1") (pintype "passive"))
      (node (ref "R17") (pin "1") (pinfunction "1_1") (pintype "passive"))
      (node (ref "REC1") (pin "1") (pinfunction "1_1") (pintype "passive"))
    )
    (net (code "84") (name "Net-(Q2-PadB)") (class "Default")
      (node (ref "Q2") (pin "B") (pintype "passive"))
      (node (ref "R12") (pin "1") (pintype "passive"))
    )
    (net (code "85") (name "Net-(Q3-PadB)") (class "Default")
      (node (ref "Q3") (pin "B") (pintype "passive"))
      (node (ref "R14") (pin "2") (pinfunction "2_2") (pintype "passive"))
      (node (ref "R8") (pin "2") (pinfunction "2_2") (pintype "passive"))
    )
    (net (code "86") (name "Net-(Q8-PadB)") (class "Default")
      (node (ref "Q8") (pin "B") (pintype "passive"))
      (node (ref "R49") (pin "2") (pintype "passive"))
    )
    (net (code "87") (name "Net-(Q9-PadB)") (class "Default")
      (node (ref "Q9") (pin "B") (pintype "passive"))
      (node (ref "R46") (pin "2") (pintype "passive"))
    )
    (net (code "88") (name "Net-(Q10-PadB)") (class "Default")
      (node (ref "Q10") (pin "B") (pintype "passive"))
      (node (ref "R50") (pin "2") (pintype "passive"))
    )
    (net (code "89") (name "Net-(U3-XTin{slash}P0.0)") (class "Default")
      (node (ref "C24") (pin "2") (pintype "passive"))
      (node (ref "OSC1") (pin "2") (pinfunction "2_2") (pintype "passive"))
      (node (ref "U3") (pin "10") (pinfunction "XTin/P0.0_10") (pintype "passive"))
    )
    (net (code "90") (name "Net-(U3-XTout{slash}P0.1)") (class "Default")
      (node (ref "C25") (pin "2") (pintype "passive"))
      (node (ref "OSC1") (pin "1") (pinfunction "1_1") (pintype "passive"))
      (node (ref "U3") (pin "11") (pinfunction "XTout/P0.1_11") (pintype "passive"))
    )
    (net (code "91") (name "Net-(WIFI-HM1)") (class "Default")
      (node (ref "R45") (pin "2") (pinfunction "2_2") (pintype "passive"))
      (node (ref "WIFI") (pin "20") (pinfunction "HM1_20") (pintype "passive"))
    )
    (net (code "92") (name "Net-(WIFI-RESET)") (class "Default")
      (node (ref "R44") (pin "1") (pinfunction "1_1") (pintype "passive"))
      (node (ref "WIFI") (pin "30") (pinfunction "RESET_30") (pintype "passive"))
    )
    (net (code "93") (name "unconnected-(LED-Pad32)") (class "Default")
      (node (ref "LED") (pin "32") (pinfunction "32_32") (pintype "passive+no_connect"))
    )
    (net (code "94") (name "unconnected-(P3-Pad3)") (class "Default")
      (node (ref "P3") (pin "3") (pinfunction "3_3") (pintype "passive"))
    )
    (net (code "95") (name "unconnected-(U2-K1-Pad2)") (class "Default")
      (node (ref "U2") (pin "2") (pinfunction "K1_2") (pintype "passive+no_connect"))
    )
    (net (code "96") (name "unconnected-(U2-K2-Pad1)") (class "Default")
      (node (ref "U2") (pin "1") (pinfunction "K2_1") (pintype "passive+no_connect"))
    )
    (net (code "97") (name "unconnected-(U2-SEG16{slash}KS16-Pad22)") (class "Default")
      (node (ref "U2") (pin "22") (pinfunction "SEG16/KS16_22") (pintype "passive+no_connect"))
    )
    (net (code "98") (name "unconnected-(U3-P0.4{slash}COM7{slash}ADC7-Pad14)") (class "Default")
      (node (ref "U3") (pin "14") (pinfunction "P0.4/COM7/ADC7_14") (pintype "passive+no_connect"))
    )
    (net (code "99") (name "unconnected-(U3-P0.5{slash}COM6{slash}ADC6-Pad16)") (class "Default")
      (node (ref "U3") (pin "16") (pinfunction "P0.5/COM6/ADC6_16") (pintype "passive"))
    )
    (net (code "100") (name "unconnected-(U3-P0.6{slash}COM5{slash}ADC5-Pad17)") (class "Default")
      (node (ref "U3") (pin "17") (pinfunction "P0.6/COM5/ADC5_17") (pintype "passive"))
    )
    (net (code "101") (name "unconnected-(U3-P2.4{slash}SEG7{slash}PG4-Pad34)") (class "Default")
      (node (ref "U3") (pin "34") (pinfunction "P2.4/SEG7/PG4_34") (pintype "passive+no_connect"))
    )
    (net (code "102") (name "unconnected-(U3-TAOUT{slash}INT1{slash}SEG19{slash}TAPWM{slash}P3.4-Pad2)") (class "Default")
      (node (ref "U3") (pin "2") (pinfunction "TAOUT/INT1/SEG19/TAPWM/P3.4_2") (pintype "passive"))
    )
    (net (code "103") (name "unconnected-(WIFI-GND-Pad9)") (class "Default")
      (node (ref "WIFI") (pin "9") (pinfunction "GND_9") (pintype "passive"))
    )
    (net (code "104") (name "unconnected-(WIFI-GND-Pad25)") (class "Default")
      (node (ref "WIFI") (pin "25") (pinfunction "GND_25") (pintype "passive"))
    )
    (net (code "105") (name "unconnected-(WIFI-GND-Pad32)") (class "Default")
      (node (ref "WIFI") (pin "32") (pinfunction "GND_32") (pintype "passive"))
    )
    (net (code "106") (name "unconnected-(WIFI-Pad3)") (class "Default")
      (node (ref "WIFI") (pin "3") (pintype "passive"))
    )
    (net (code "107") (name "unconnected-(WIFI-Pad5)") (class "Default")
      (node (ref "WIFI") (pin "5") (pintype "passive"))
    )
    (net (code "108") (name "unconnected-(WIFI-Pad6)") (class "Default")
      (node (ref "WIFI") (pin "6") (pintype "passive"))
    )
    (net (code "109") (name "unconnected-(WIFI-Pad7)") (class "Default")
      (node (ref "WIFI") (pin "7") (pintype "passive"))
    )
    (net (code "110") (name "unconnected-(WIFI-Pad8)") (class "Default")
      (node (ref "WIFI") (pin "8") (pintype "passive"))
    )
    (net (code "111") (name "unconnected-(WIFI-Pad10)") (class "Default")
      (node (ref "WIFI") (pin "10") (pintype "passive"))
    )
    (net (code "112") (name "unconnected-(WIFI-Pad11)") (class "Default")
      (node (ref "WIFI") (pin "11") (pintype "passive"))
    )
    (net (code "113") (name "unconnected-(WIFI-Pad14)") (class "Default")
      (node (ref "WIFI") (pin "14") (pintype "passive"))
    )
    (net (code "114") (name "unconnected-(WIFI-Pad15)") (class "Default")
      (node (ref "WIFI") (pin "15") (pintype "passive"))
    )
    (net (code "115") (name "unconnected-(WIFI-Pad16)") (class "Default")
      (node (ref "WIFI") (pin "16") (pintype "passive"))
    )
    (net (code "116") (name "unconnected-(WIFI-Pad17)") (class "Default")
      (node (ref "WIFI") (pin "17") (pintype "passive"))
    )
    (net (code "117") (name "unconnected-(WIFI-Pad19)") (class "Default")
      (node (ref "WIFI") (pin "19") (pintype "passive"))
    )
    (net (code "118") (name "unconnected-(WIFI-Pad21)") (class "Default")
      (node (ref "WIFI") (pin "21") (pintype "passive"))
    )
    (net (code "119") (name "unconnected-(WIFI-Pad22)") (class "Default")
      (node (ref "WIFI") (pin "22") (pintype "passive"))
    )
    (net (code "120") (name "unconnected-(WIFI-Pad23)") (class "Default")
      (node (ref "WIFI") (pin "23") (pintype "passive"))
    )
    (net (code "121") (name "unconnected-(WIFI-Pad24)") (class "Default")
      (node (ref "WIFI") (pin "24") (pintype "passive"))
    )
    (net (code "122") (name "unconnected-(WIFI-Pad27)") (class "Default")
      (node (ref "WIFI") (pin "27") (pintype "passive"))
    )
    (net (code "123") (name "unconnected-(WIFI-Pad28)") (class "Default")
      (node (ref "WIFI") (pin "28") (pintype "passive"))
    )
    (net (code "124") (name "unconnected-(WIFI-Pad29)") (class "Default")
      (node (ref "WIFI") (pin "29") (pintype "passive"))
    )
    (net (code "125") (name "unconnected-(WIFI-Pad31)") (class "Default")
      (node (ref "WIFI") (pin "31") (pintype "passive"))
    )
    (net (code "126") (name "unconnected-(WIFI-Pad33)") (class "Default")
      (node (ref "WIFI") (pin "33") (pintype "passive"))
    )
    (net (code "127") (name "unconnected-(WIFI-VCC-Pad2)") (class "Default")
      (node (ref "WIFI") (pin "2") (pinfunction "VCC_2") (pintype "passive"))
    )
    (net (code "128") (name "unconnected-(WIFI-VCC-Pad13)") (class "Default")
      (node (ref "WIFI") (pin "13") (pinfunction "VCC_13") (pintype "passive"))
    )
  )
)
